# PI_Shield.net
KiCad netlist of a schematic drawn in EAGLE
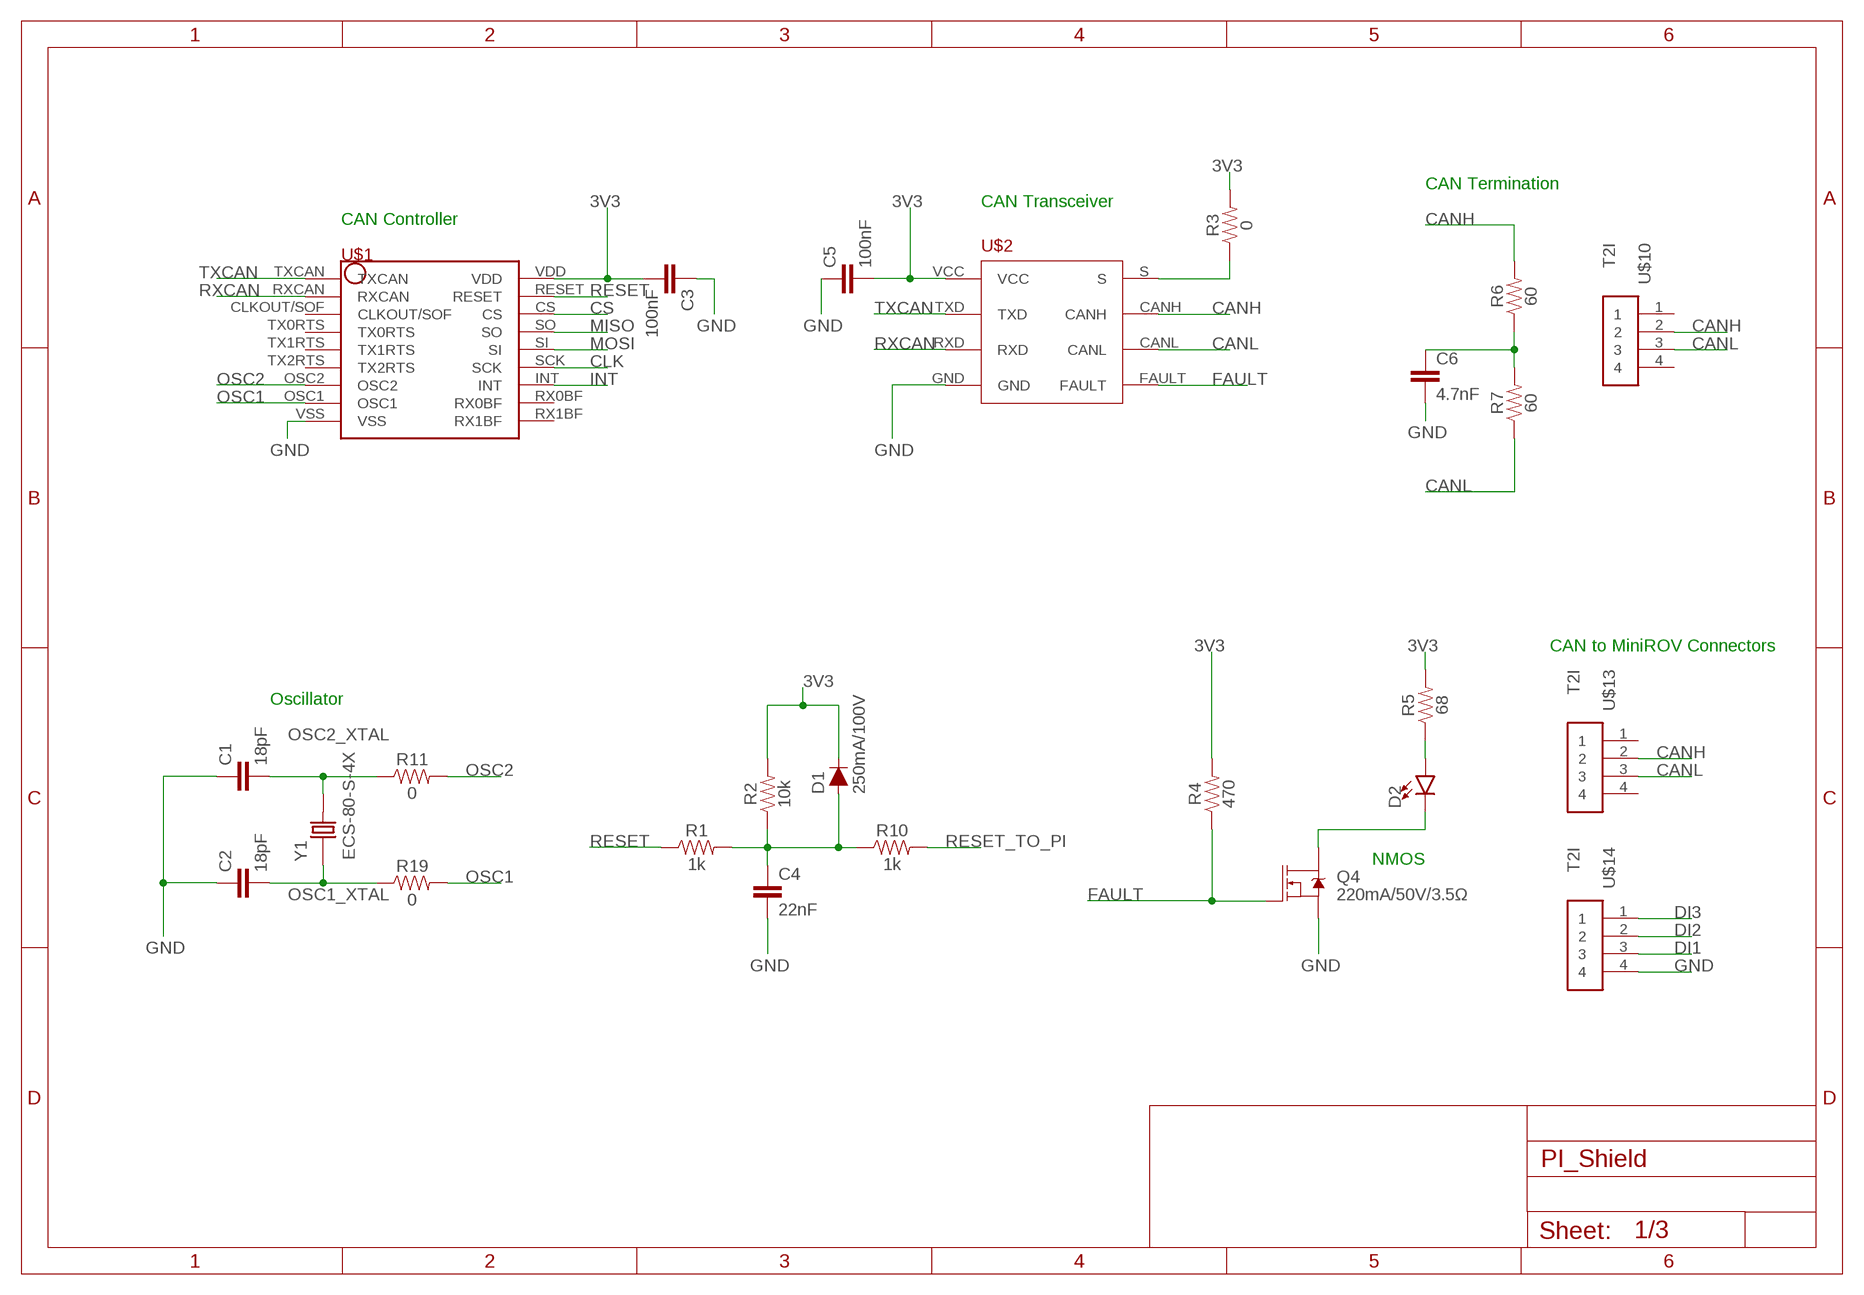
[diagram p0: schematic, sheet 1]
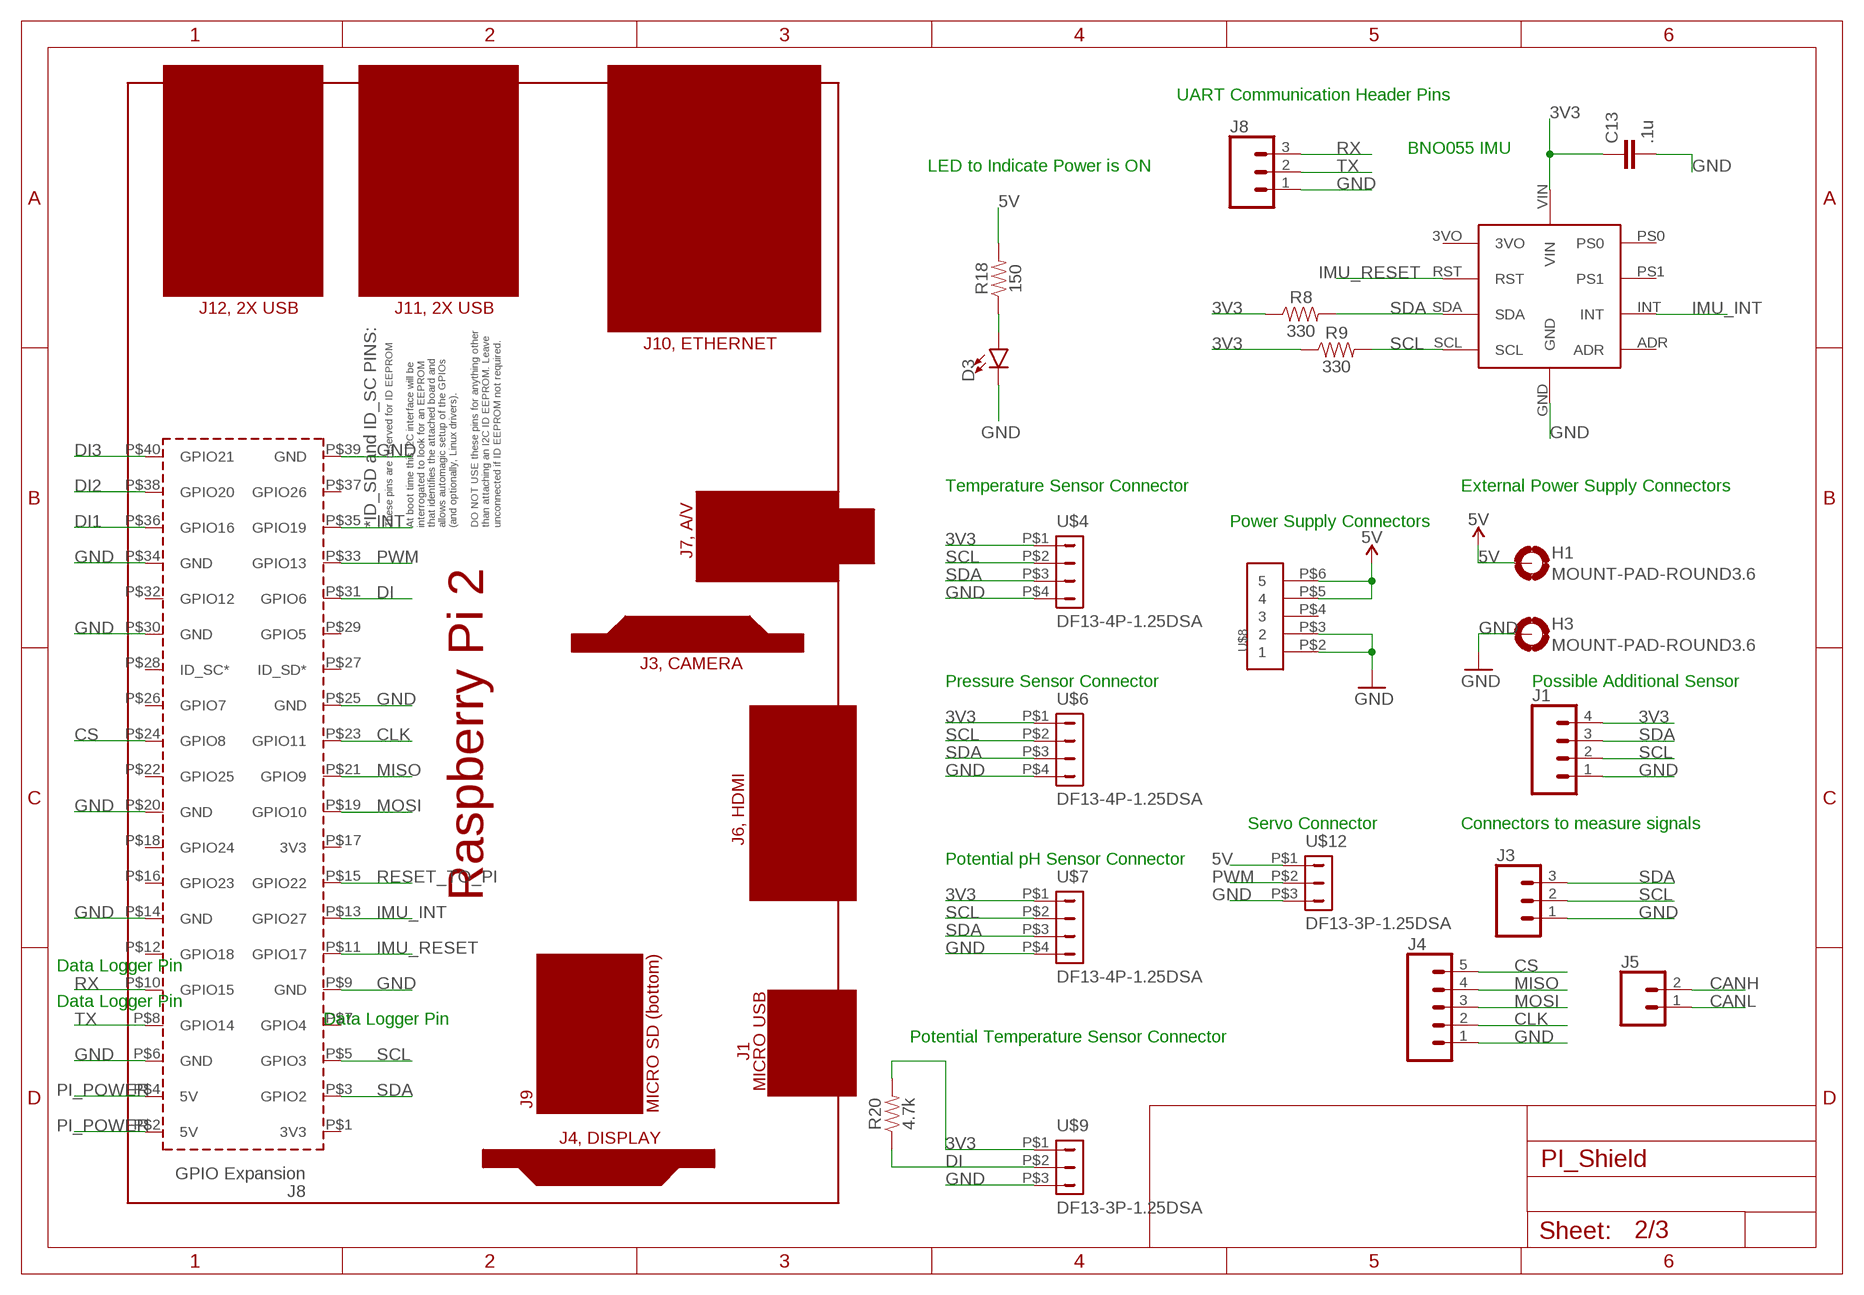
[diagram p1: schematic, sheet 2]
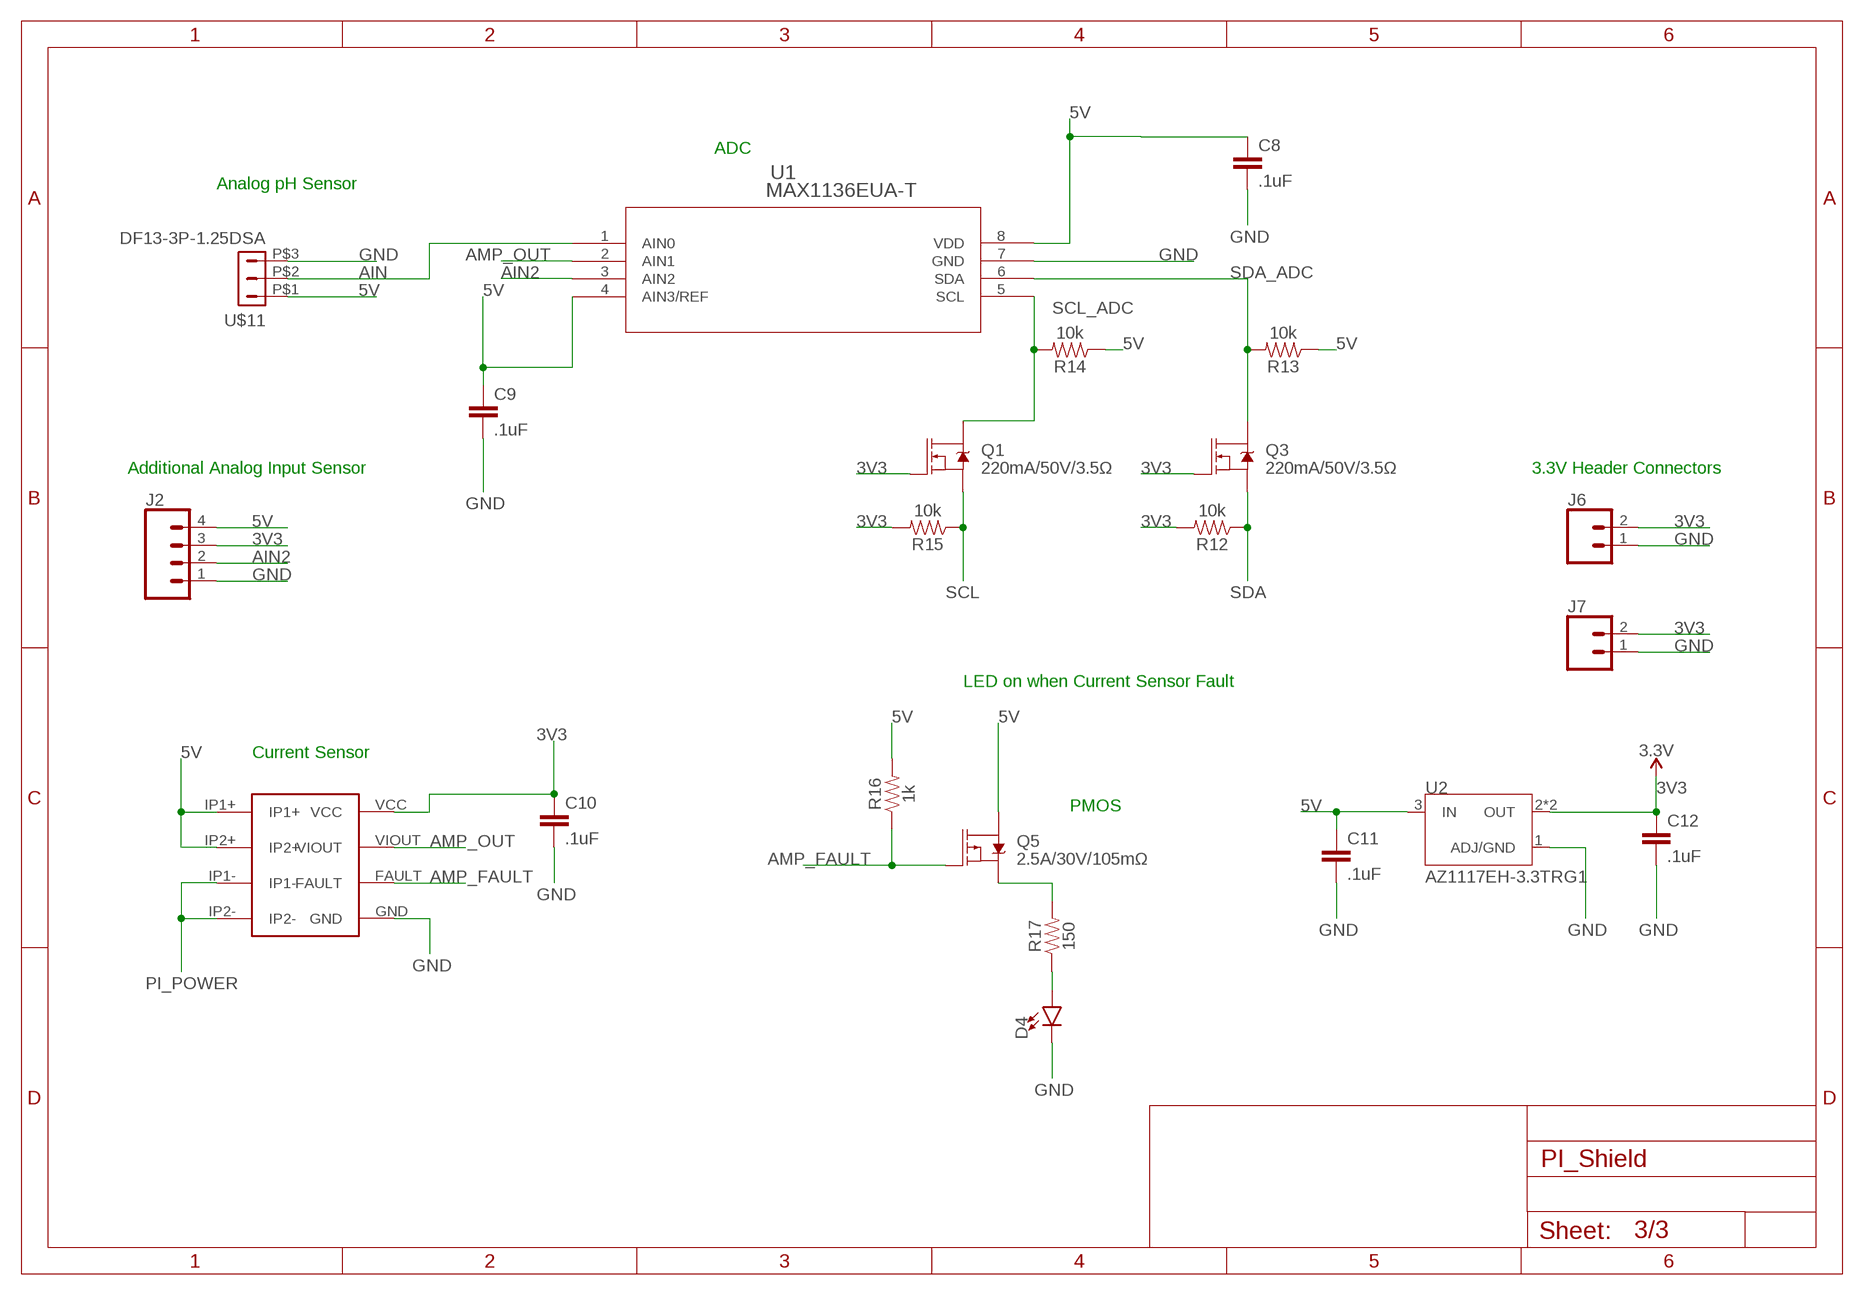
[diagram p2: schematic, sheet 3]

(export (version "E")
  (design (tool "Eeschema 10.0.6"))
  (components
    (comp (ref "C8")
      (value ".1uF")
      (footprint "eagle-import:0603")
      (libsource (lib "eagle-import") (part "22NF/22,000PF-0603-50V-10%"))
    )
    (comp (ref "C9")
      (value ".1uF")
      (footprint "eagle-import:0603")
      (libsource (lib "eagle-import") (part "22NF/22,000PF-0603-50V-10%"))
    )
    (comp (ref "C10")
      (value ".1uF")
      (footprint "eagle-import:0603")
      (libsource (lib "eagle-import") (part "22NF/22,000PF-0603-50V-10%"))
    )
    (comp (ref "C11")
      (value ".1uF")
      (footprint "eagle-import:0603")
      (libsource (lib "eagle-import") (part "22NF/22,000PF-0603-50V-10%"))
    )
    (comp (ref "C12")
      (value ".1uF")
      (footprint "eagle-import:0603")
      (libsource (lib "eagle-import") (part "22NF/22,000PF-0603-50V-10%"))
    )
    (comp (ref "D4")
      (value "LED0603")
      (footprint "eagle-import:LED-0603")
      (libsource (lib "eagle-import") (part "LED0603"))
    )
    (comp (ref "J2")
      (value "CONN_04")
      (footprint "eagle-import:1X04")
      (libsource (lib "eagle-import") (part "CONN_04"))
    )
    (comp (ref "J6")
      (value "CONN_02")
      (footprint "eagle-import:1X02")
      (libsource (lib "eagle-import") (part "CONN_02"))
    )
    (comp (ref "J7")
      (value "CONN_02")
      (footprint "eagle-import:1X02")
      (libsource (lib "eagle-import") (part "CONN_02"))
    )
    (comp (ref "Q1")
      (value "220mA/50V/3.5Ω")
      (footprint "eagle-import:SOT23-3")
      (libsource (lib "eagle-import") (part "MOSFET-NCH-BSS138"))
    )
    (comp (ref "Q3")
      (value "220mA/50V/3.5Ω")
      (footprint "eagle-import:SOT23-3")
      (libsource (lib "eagle-import") (part "MOSFET-NCH-BSS138"))
    )
    (comp (ref "Q5")
      (value "2.5A/30V/105mΩ")
      (footprint "eagle-import:SOT23-3")
      (libsource (lib "eagle-import") (part "MOSFET_PCH-DMG2307L"))
    )
    (comp (ref "R12")
      (value "10k")
      (footprint "eagle-import:0603")
      (libsource (lib "eagle-import") (part "RESISTOR0603"))
    )
    (comp (ref "R13")
      (value "10k")
      (footprint "eagle-import:0603")
      (libsource (lib "eagle-import") (part "RESISTOR0603"))
    )
    (comp (ref "R14")
      (value "10k")
      (footprint "eagle-import:0603")
      (libsource (lib "eagle-import") (part "RESISTOR0603"))
    )
    (comp (ref "R15")
      (value "10k")
      (footprint "eagle-import:0603")
      (libsource (lib "eagle-import") (part "RESISTOR0603"))
    )
    (comp (ref "R16")
      (value "1k")
      (footprint "eagle-import:0603")
      (libsource (lib "eagle-import") (part "RESISTOR0603"))
    )
    (comp (ref "R17")
      (value "150")
      (footprint "eagle-import:0603")
      (libsource (lib "eagle-import") (part "RESISTOR0603"))
    )
    (comp (ref "U$5")
      (value "ACS711")
      (footprint "eagle-import:ACS711")
      (libsource (lib "eagle-import") (part "ACS711"))
    )
    (comp (ref "U$11")
      (value "DF13-3P-1.25DSA")
      (footprint "eagle-import:DF13-3P-1.25DSA")
      (libsource (lib "eagle-import") (part "DF13-3P-1.25DSA"))
    )
    (comp (ref "U1")
      (value "MAX1136EUA-T")
      (footprint "eagle-import:21-0036K")
      (fields
        (field (name "DIGI-KEY_PART_NUMBER") "MAX1136EUA+-ND")
        (field (name "MF") "Maxim Integrated")
        (field (name "MP") "MAX1136EUA+")
      )
      (libsource (lib "eagle-import") (part "MAX1136EUA-T"))
    )
    (comp (ref "U2")
      (value "AZ1117EH-3.3TRG1")
      (footprint "eagle-import:SOT230P700X180-4N")
      (fields (field (name "MF") "Diodes Inc."))
      (libsource (lib "eagle-import") (part "AZ1117EH-3.3TRG1"))
    )
    (comp (ref "C1")
      (value "18pF")
      (footprint "eagle-import:0603")
      (libsource (lib "eagle-import") (part "22PF-0603-50V-5%"))
    )
    (comp (ref "C2")
      (value "18pF")
      (footprint "eagle-import:0603")
      (libsource (lib "eagle-import") (part "22PF-0603-50V-5%"))
    )
    (comp (ref "C3")
      (value "100nF")
      (footprint "eagle-import:0603")
      (libsource (lib "eagle-import") (part "22NF/22,000PF-0603-50V-10%"))
    )
    (comp (ref "C4")
      (value "22nF")
      (footprint "eagle-import:0603")
      (libsource (lib "eagle-import") (part "22NF/22,000PF-0603-50V-10%"))
    )
    (comp (ref "C5")
      (value "100nF")
      (footprint "eagle-import:0603")
      (libsource (lib "eagle-import") (part "22NF/22,000PF-0603-50V-10%"))
    )
    (comp (ref "C6")
      (value "4.7nF")
      (footprint "eagle-import:0603")
      (libsource (lib "eagle-import") (part "22NF/22,000PF-0603-50V-10%"))
    )
    (comp (ref "D1")
      (value "250mA/100V")
      (footprint "eagle-import:SOD-323")
      (libsource (lib "eagle-import") (part "DIODE-BAS16J"))
    )
    (comp (ref "D2")
      (value "LED0603")
      (footprint "eagle-import:LED-0603")
      (libsource (lib "eagle-import") (part "LED0603"))
    )
    (comp (ref "Q4")
      (value "220mA/50V/3.5Ω")
      (footprint "eagle-import:SOT23-3")
      (libsource (lib "eagle-import") (part "MOSFET-NCH-BSS138"))
    )
    (comp (ref "R1")
      (value "1k")
      (footprint "eagle-import:0603")
      (libsource (lib "eagle-import") (part "RESISTOR0603"))
    )
    (comp (ref "R2")
      (value "10k")
      (footprint "eagle-import:0603")
      (libsource (lib "eagle-import") (part "RESISTOR0603"))
    )
    (comp (ref "R3")
      (value "0")
      (footprint "eagle-import:0603")
      (libsource (lib "eagle-import") (part "RESISTOR0603"))
    )
    (comp (ref "R4")
      (value "470")
      (footprint "eagle-import:0603")
      (libsource (lib "eagle-import") (part "RESISTOR0603"))
    )
    (comp (ref "R5")
      (value "68")
      (footprint "eagle-import:0603")
      (libsource (lib "eagle-import") (part "RESISTOR0603"))
    )
    (comp (ref "R6")
      (value "60")
      (footprint "eagle-import:0603")
      (libsource (lib "eagle-import") (part "RESISTOR0603"))
    )
    (comp (ref "R7")
      (value "60")
      (footprint "eagle-import:0603")
      (libsource (lib "eagle-import") (part "RESISTOR0603"))
    )
    (comp (ref "R10")
      (value "1k")
      (footprint "eagle-import:0603")
      (libsource (lib "eagle-import") (part "RESISTOR0603"))
    )
    (comp (ref "R11")
      (value "0")
      (footprint "eagle-import:0603")
      (libsource (lib "eagle-import") (part "RESISTOR0603"))
    )
    (comp (ref "R19")
      (value "0")
      (footprint "eagle-import:0603")
      (libsource (lib "eagle-import") (part "RESISTOR0603"))
    )
    (comp (ref "U$1")
      (value "MCP2515")
      (footprint "eagle-import:MCP2515")
      (libsource (lib "eagle-import") (part "MCP2515"))
    )
    (comp (ref "U$2")
      (value "TCAN337D")
      (footprint "eagle-import:TCAN337D")
      (libsource (lib "eagle-import") (part "TCAN337D"))
    )
    (comp (ref "U$10")
      (value "T2I")
      (footprint "eagle-import:T2I")
      (libsource (lib "eagle-import") (part "T2I"))
    )
    (comp (ref "U$13")
      (value "T2I")
      (footprint "eagle-import:T2I")
      (libsource (lib "eagle-import") (part "T2I"))
    )
    (comp (ref "U$14")
      (value "T2I")
      (footprint "eagle-import:T2I")
      (libsource (lib "eagle-import") (part "T2I"))
    )
    (comp (ref "Y1")
      (value "ECS-80-S-4X")
      (footprint "eagle-import:XTAL_ECS-80-S-4X")
      (fields (field (name "DIGI-KEY_PART_NUMBER") "X1057-ND") (field (name "MF") "ECS International"))
      (libsource (lib "eagle-import") (part "ECS-80-S-4X"))
    )
    (comp (ref "C13")
      (value ".1u")
      (footprint "eagle-import:0603")
      (libsource (lib "eagle-import") (part "22NF/22,000PF-0603-50V-10%"))
    )
    (comp (ref "D3")
      (value "LED0603")
      (footprint "eagle-import:LED-0603")
      (libsource (lib "eagle-import") (part "LED0603"))
    )
    (comp (ref "H1")
      (value "MOUNT-PAD-ROUND3.6")
      (footprint "eagle-import:3,6-PAD")
      (libsource (lib "eagle-import") (part "MOUNT-PAD-ROUND3.6"))
    )
    (comp (ref "H3")
      (value "MOUNT-PAD-ROUND3.6")
      (footprint "eagle-import:3,6-PAD")
      (libsource (lib "eagle-import") (part "MOUNT-PAD-ROUND3.6"))
    )
    (comp (ref "J1")
      (value "CONN_04")
      (footprint "eagle-import:1X04")
      (libsource (lib "eagle-import") (part "CONN_04"))
    )
    (comp (ref "J3")
      (value "CONN_03")
      (footprint "eagle-import:1X03")
      (libsource (lib "eagle-import") (part "CONN_03"))
    )
    (comp (ref "J4")
      (value "CONN_05")
      (footprint "eagle-import:1X05")
      (libsource (lib "eagle-import") (part "CONN_05"))
    )
    (comp (ref "J5")
      (value "CONN_02")
      (footprint "eagle-import:1X02")
      (libsource (lib "eagle-import") (part "SparkFun-Connectors_513_CONN_02"))
    )
    (comp (ref "J8")
      (value "CONN_03")
      (footprint "eagle-import:1X03")
      (libsource (lib "eagle-import") (part "CONN_03"))
    )
    (comp (ref "PCB1")
      (value "RPI2")
      (footprint "eagle-import:RPI2")
      (libsource (lib "eagle-import") (part "RPI2"))
    )
    (comp (ref "R8")
      (value "330")
      (footprint "eagle-import:0603")
      (libsource (lib "eagle-import") (part "RESISTOR0603"))
    )
    (comp (ref "R9")
      (value "330")
      (footprint "eagle-import:0603")
      (libsource (lib "eagle-import") (part "RESISTOR0603"))
    )
    (comp (ref "R18")
      (value "150")
      (footprint "eagle-import:0603")
      (libsource (lib "eagle-import") (part "RESISTOR0603"))
    )
    (comp (ref "R20")
      (value "4.7k")
      (footprint "eagle-import:0603")
      (libsource (lib "eagle-import") (part "RESISTOR0603"))
    )
    (comp (ref "U$3")
      (value "BNO055_9DOF_BREAKOUT")
      (footprint "eagle-import:BNO055")
      (libsource (lib "eagle-import") (part "BNO055_9DOF_BREAKOUT"))
    )
    (comp (ref "U$4")
      (value "DF13-4P-1.25DSA")
      (footprint "eagle-import:DF13-4P-1.25DSA")
      (libsource (lib "eagle-import") (part "DF13-4P-1.25DSA"))
    )
    (comp (ref "U$6")
      (value "DF13-4P-1.25DSA")
      (footprint "eagle-import:DF13-4P-1.25DSA")
      (libsource (lib "eagle-import") (part "DF13-4P-1.25DSA"))
    )
    (comp (ref "U$7")
      (value "DF13-4P-1.25DSA")
      (footprint "eagle-import:DF13-4P-1.25DSA")
      (libsource (lib "eagle-import") (part "DF13-4P-1.25DSA"))
    )
    (comp (ref "U$8")
      (value "T2I5P")
      (footprint "eagle-import:T2I5P")
      (libsource (lib "eagle-import") (part "T2I5P"))
    )
    (comp (ref "U$9")
      (value "DF13-3P-1.25DSA")
      (footprint "eagle-import:DF13-3P-1.25DSA")
      (libsource (lib "eagle-import") (part "DF13-3P-1.25DSA"))
    )
    (comp (ref "U$12")
      (value "DF13-3P-1.25DSA")
      (footprint "eagle-import:DF13-3P-1.25DSA")
      (libsource (lib "eagle-import") (part "DF13-3P-1.25DSA"))
    )
  )
  (nets
    (net (code "1") (name "3V3") (class "Default")
      (node (ref "C10") (pin "1") (pinfunction "1_1") (pintype "passive"))
      (node (ref "C12") (pin "1") (pinfunction "1_1") (pintype "passive"))
      (node (ref "C13") (pin "1") (pinfunction "1_1") (pintype "passive"))
      (node (ref "C3") (pin "2") (pinfunction "2_2") (pintype "passive"))
      (node (ref "C5") (pin "2") (pinfunction "2_2") (pintype "passive"))
      (node (ref "D1") (pin "C") (pinfunction "C_C") (pintype "passive"))
      (node (ref "J1") (pin "4") (pinfunction "4_4") (pintype "passive"))
      (node (ref "J2") (pin "3") (pinfunction "3_3") (pintype "passive"))
      (node (ref "J6") (pin "2") (pinfunction "2_2") (pintype "passive"))
      (node (ref "J7") (pin "2") (pinfunction "2_2") (pintype "passive"))
      (node (ref "Q1") (pin "1") (pinfunction "G_1") (pintype "bidirectional"))
      (node (ref "Q3") (pin "1") (pinfunction "G_1") (pintype "bidirectional"))
      (node (ref "R12") (pin "2") (pinfunction "2_2") (pintype "passive"))
      (node (ref "R15") (pin "2") (pinfunction "2_2") (pintype "passive"))
      (node (ref "R2") (pin "2") (pinfunction "2_2") (pintype "passive"))
      (node (ref "R20") (pin "2") (pinfunction "2_2") (pintype "passive"))
      (node (ref "R3") (pin "2") (pinfunction "2_2") (pintype "passive"))
      (node (ref "R4") (pin "2") (pinfunction "2_2") (pintype "passive"))
      (node (ref "R5") (pin "2") (pinfunction "2_2") (pintype "passive"))
      (node (ref "R8") (pin "1") (pinfunction "1_1") (pintype "passive"))
      (node (ref "R9") (pin "1") (pinfunction "1_1") (pintype "passive"))
      (node (ref "U$1") (pin "VDD") (pinfunction "VDD_VDD") (pintype "bidirectional"))
      (node (ref "U$2") (pin "VCC") (pinfunction "VCC_VCC") (pintype "bidirectional"))
      (node (ref "U$3") (pin "VIN") (pinfunction "VIN_VIN") (pintype "bidirectional"))
      (node (ref "U$4") (pin "P$1") (pinfunction "1_P$1") (pintype "passive"))
      (node (ref "U$5") (pin "VCC") (pinfunction "VCC_VCC") (pintype "bidirectional"))
      (node (ref "U$6") (pin "P$1") (pinfunction "1_P$1") (pintype "passive"))
      (node (ref "U$7") (pin "P$1") (pinfunction "1_P$1") (pintype "passive"))
      (node (ref "U$9") (pin "P$1") (pinfunction "1_P$1") (pintype "passive"))
      (node (ref "U2") (pin "2") (pinfunction "OUT_2") (pintype "output"))
      (node (ref "U2") (pin "4") (pinfunction "OUT_4") (pintype "output"))
    )
    (net (code "2") (name "5V") (class "Default")
      (node (ref "C11") (pin "1") (pinfunction "1_1") (pintype "passive"))
      (node (ref "C8") (pin "1") (pinfunction "1_1") (pintype "passive"))
      (node (ref "C9") (pin "1") (pinfunction "1_1") (pintype "passive"))
      (node (ref "H1") (pin "B3,6") (pinfunction "MOUNT_B3,6") (pintype "passive"))
      (node (ref "J2") (pin "4") (pinfunction "4_4") (pintype "passive"))
      (node (ref "Q5") (pin "3") (pinfunction "D_3") (pintype "bidirectional"))
      (node (ref "R13") (pin "1") (pinfunction "1_1") (pintype "passive"))
      (node (ref "R14") (pin "1") (pinfunction "1_1") (pintype "passive"))
      (node (ref "R16") (pin "2") (pinfunction "2_2") (pintype "passive"))
      (node (ref "R18") (pin "2") (pinfunction "2_2") (pintype "passive"))
      (node (ref "U$11") (pin "P$1") (pinfunction "1_P$1") (pintype "passive"))
      (node (ref "U$12") (pin "P$1") (pinfunction "1_P$1") (pintype "passive"))
      (node (ref "U$5") (pin "IP1+") (pinfunction "IP1+_IP1+") (pintype "bidirectional"))
      (node (ref "U$5") (pin "IP2+") (pinfunction "IP2+_IP2+") (pintype "bidirectional"))
      (node (ref "U$8") (pin "P$5") (pinfunction "4_P$5") (pintype "bidirectional"))
      (node (ref "U$8") (pin "P$6") (pinfunction "5_P$6") (pintype "bidirectional"))
      (node (ref "U1") (pin "4") (pinfunction "AIN3/REF_4") (pintype "bidirectional"))
      (node (ref "U1") (pin "8") (pinfunction "VDD_8") (pintype "power_in"))
      (node (ref "U2") (pin "3") (pinfunction "IN_3") (pintype "input"))
    )
    (net (code "3") (name "AIN") (class "Default")
      (node (ref "U$11") (pin "P$2") (pinfunction "2_P$2") (pintype "passive"))
      (node (ref "U1") (pin "1") (pinfunction "AIN0_1") (pintype "bidirectional"))
    )
    (net (code "4") (name "AIN2") (class "Default")
      (node (ref "J2") (pin "2") (pinfunction "2_2") (pintype "passive"))
      (node (ref "U1") (pin "3") (pinfunction "AIN2_3") (pintype "bidirectional"))
    )
    (net (code "5") (name "AMP_FAULT") (class "Default")
      (node (ref "Q5") (pin "1") (pinfunction "G_1") (pintype "bidirectional"))
      (node (ref "R16") (pin "1") (pinfunction "1_1") (pintype "passive"))
      (node (ref "U$5") (pin "FAULT") (pinfunction "FAULT_FAULT") (pintype "bidirectional"))
    )
    (net (code "6") (name "AMP_OUT") (class "Default")
      (node (ref "U$5") (pin "VIOUT") (pinfunction "VIOUT_VIOUT") (pintype "bidirectional"))
      (node (ref "U1") (pin "2") (pinfunction "AIN1_2") (pintype "bidirectional"))
    )
    (net (code "7") (name "CANH") (class "Default")
      (node (ref "J5") (pin "2") (pinfunction "2_2") (pintype "passive"))
      (node (ref "R6") (pin "2") (pinfunction "2_2") (pintype "passive"))
      (node (ref "U$10") (pin "2") (pinfunction "2_2") (pintype "bidirectional"))
      (node (ref "U$13") (pin "2") (pinfunction "2_2") (pintype "bidirectional"))
      (node (ref "U$2") (pin "CANH") (pinfunction "CANH_CANH") (pintype "bidirectional"))
    )
    (net (code "8") (name "CANL") (class "Default")
      (node (ref "J5") (pin "1") (pinfunction "1_1") (pintype "passive"))
      (node (ref "R7") (pin "1") (pinfunction "1_1") (pintype "passive"))
      (node (ref "U$10") (pin "3") (pinfunction "3_3") (pintype "bidirectional"))
      (node (ref "U$13") (pin "3") (pinfunction "3_3") (pintype "bidirectional"))
      (node (ref "U$2") (pin "CANL") (pinfunction "CANL_CANL") (pintype "bidirectional"))
    )
    (net (code "9") (name "CLK") (class "Default")
      (node (ref "J4") (pin "2") (pinfunction "2_2") (pintype "passive"))
      (node (ref "PCB1") (pin "P$23") (pinfunction "GPIO11_P$23") (pintype "bidirectional"))
      (node (ref "U$1") (pin "SCK") (pinfunction "SCK_SCK") (pintype "bidirectional"))
    )
    (net (code "10") (name "CS") (class "Default")
      (node (ref "J4") (pin "5") (pinfunction "5_5") (pintype "passive"))
      (node (ref "PCB1") (pin "P$24") (pinfunction "GPIO8_P$24") (pintype "bidirectional"))
      (node (ref "U$1") (pin "CS") (pinfunction "CS_CS") (pintype "bidirectional"))
    )
    (net (code "11") (name "DI") (class "Default")
      (node (ref "PCB1") (pin "P$31") (pinfunction "GPIO6_P$31") (pintype "bidirectional"))
      (node (ref "R20") (pin "1") (pinfunction "1_1") (pintype "passive"))
      (node (ref "U$9") (pin "P$2") (pinfunction "2_P$2") (pintype "passive"))
    )
    (net (code "12") (name "DI1") (class "Default")
      (node (ref "PCB1") (pin "P$36") (pinfunction "GPIO16_P$36") (pintype "bidirectional"))
      (node (ref "U$14") (pin "3") (pinfunction "3_3") (pintype "bidirectional"))
    )
    (net (code "13") (name "DI2") (class "Default")
      (node (ref "PCB1") (pin "P$38") (pinfunction "GPIO20_P$38") (pintype "bidirectional"))
      (node (ref "U$14") (pin "2") (pinfunction "2_2") (pintype "bidirectional"))
    )
    (net (code "14") (name "DI3") (class "Default")
      (node (ref "PCB1") (pin "P$40") (pinfunction "GPIO21_P$40") (pintype "bidirectional"))
      (node (ref "U$14") (pin "1") (pinfunction "1_1") (pintype "bidirectional"))
    )
    (net (code "15") (name "FAULT") (class "Default")
      (node (ref "Q4") (pin "1") (pinfunction "G_1") (pintype "bidirectional"))
      (node (ref "R4") (pin "1") (pinfunction "1_1") (pintype "passive"))
      (node (ref "U$2") (pin "FAULT") (pinfunction "FAULT_FAULT") (pintype "bidirectional"))
    )
    (net (code "16") (name "GND") (class "Default")
      (node (ref "C1") (pin "1") (pinfunction "1_1") (pintype "passive"))
      (node (ref "C10") (pin "2") (pinfunction "2_2") (pintype "passive"))
      (node (ref "C11") (pin "2") (pinfunction "2_2") (pintype "passive"))
      (node (ref "C12") (pin "2") (pinfunction "2_2") (pintype "passive"))
      (node (ref "C13") (pin "2") (pinfunction "2_2") (pintype "passive"))
      (node (ref "C2") (pin "1") (pinfunction "1_1") (pintype "passive"))
      (node (ref "C3") (pin "1") (pinfunction "1_1") (pintype "passive"))
      (node (ref "C4") (pin "2") (pinfunction "2_2") (pintype "passive"))
      (node (ref "C5") (pin "1") (pinfunction "1_1") (pintype "passive"))
      (node (ref "C6") (pin "2") (pinfunction "2_2") (pintype "passive"))
      (node (ref "C8") (pin "2") (pinfunction "2_2") (pintype "passive"))
      (node (ref "C9") (pin "2") (pinfunction "2_2") (pintype "passive"))
      (node (ref "D3") (pin "C") (pinfunction "C_C") (pintype "passive"))
      (node (ref "D4") (pin "C") (pinfunction "C_C") (pintype "passive"))
      (node (ref "H3") (pin "B3,6") (pinfunction "MOUNT_B3,6") (pintype "passive"))
      (node (ref "J1") (pin "1") (pinfunction "1_1") (pintype "passive"))
      (node (ref "J2") (pin "1") (pinfunction "1_1") (pintype "passive"))
      (node (ref "J3") (pin "1") (pinfunction "1_1") (pintype "passive"))
      (node (ref "J4") (pin "1") (pinfunction "1_1") (pintype "passive"))
      (node (ref "J6") (pin "1") (pinfunction "1_1") (pintype "passive"))
      (node (ref "J7") (pin "1") (pinfunction "1_1") (pintype "passive"))
      (node (ref "J8") (pin "1") (pinfunction "1_1") (pintype "passive"))
      (node (ref "PCB1") (pin "P$14") (pinfunction "GND_P$14") (pintype "bidirectional"))
      (node (ref "PCB1") (pin "P$20") (pinfunction "GND_P$20") (pintype "bidirectional"))
      (node (ref "PCB1") (pin "P$25") (pinfunction "GND_P$25") (pintype "bidirectional"))
      (node (ref "PCB1") (pin "P$30") (pinfunction "GND_P$30") (pintype "bidirectional"))
      (node (ref "PCB1") (pin "P$34") (pinfunction "GND_P$34") (pintype "bidirectional"))
      (node (ref "PCB1") (pin "P$39") (pinfunction "GND_P$39") (pintype "bidirectional"))
      (node (ref "PCB1") (pin "P$6") (pinfunction "GND_P$6") (pintype "bidirectional"))
      (node (ref "PCB1") (pin "P$9") (pinfunction "GND_P$9") (pintype "bidirectional"))
      (node (ref "Q4") (pin "2") (pinfunction "S_2") (pintype "bidirectional"))
      (node (ref "U$1") (pin "VSS") (pinfunction "VSS_VSS") (pintype "bidirectional"))
      (node (ref "U$11") (pin "P$3") (pinfunction "3_P$3") (pintype "passive"))
      (node (ref "U$12") (pin "P$3") (pinfunction "3_P$3") (pintype "passive"))
      (node (ref "U$14") (pin "4") (pinfunction "4_4") (pintype "bidirectional"))
      (node (ref "U$2") (pin "GND") (pinfunction "GND_GND") (pintype "bidirectional"))
      (node (ref "U$3") (pin "GND") (pinfunction "GND_GND") (pintype "bidirectional"))
      (node (ref "U$4") (pin "P$4") (pinfunction "4_P$4") (pintype "passive"))
      (node (ref "U$5") (pin "GND") (pinfunction "GND_GND") (pintype "bidirectional"))
      (node (ref "U$6") (pin "P$4") (pinfunction "4_P$4") (pintype "passive"))
      (node (ref "U$7") (pin "P$4") (pinfunction "4_P$4") (pintype "passive"))
      (node (ref "U$8") (pin "P$2") (pinfunction "1_P$2") (pintype "bidirectional"))
      (node (ref "U$8") (pin "P$3") (pinfunction "2_P$3") (pintype "bidirectional"))
      (node (ref "U$9") (pin "P$3") (pinfunction "3_P$3") (pintype "passive"))
      (node (ref "U1") (pin "7") (pinfunction "GND_7") (pintype "power_in"))
      (node (ref "U2") (pin "1") (pinfunction "ADJ/GND_1") (pintype "power_in"))
    )
    (net (code "17") (name "IMU_INT") (class "Default")
      (node (ref "PCB1") (pin "P$13") (pinfunction "GPIO27_P$13") (pintype "bidirectional"))
      (node (ref "U$3") (pin "INT") (pinfunction "INT_INT") (pintype "bidirectional"))
    )
    (net (code "18") (name "IMU_RESET") (class "Default")
      (node (ref "PCB1") (pin "P$11") (pinfunction "GPIO17_P$11") (pintype "bidirectional"))
      (node (ref "U$3") (pin "RST") (pinfunction "RST_RST") (pintype "bidirectional"))
    )
    (net (code "19") (name "INT") (class "Default")
      (node (ref "PCB1") (pin "P$35") (pinfunction "GPIO19_P$35") (pintype "bidirectional"))
      (node (ref "U$1") (pin "INT") (pinfunction "INT_INT") (pintype "bidirectional"))
    )
    (net (code "20") (name "MISO") (class "Default")
      (node (ref "J4") (pin "4") (pinfunction "4_4") (pintype "passive"))
      (node (ref "PCB1") (pin "P$21") (pinfunction "GPIO9_P$21") (pintype "bidirectional"))
      (node (ref "U$1") (pin "SO") (pinfunction "SO_SO") (pintype "bidirectional"))
    )
    (net (code "21") (name "MOSI") (class "Default")
      (node (ref "J4") (pin "3") (pinfunction "3_3") (pintype "passive"))
      (node (ref "PCB1") (pin "P$19") (pinfunction "GPIO10_P$19") (pintype "bidirectional"))
      (node (ref "U$1") (pin "SI") (pinfunction "SI_SI") (pintype "bidirectional"))
    )
    (net (code "22") (name "Net-(C4-Pad1)") (class "Default")
      (node (ref "C4") (pin "1") (pinfunction "1_1") (pintype "passive"))
      (node (ref "D1") (pin "A") (pinfunction "A_A") (pintype "passive"))
      (node (ref "R1") (pin "2") (pinfunction "2_2") (pintype "passive"))
      (node (ref "R10") (pin "1") (pinfunction "1_1") (pintype "passive"))
      (node (ref "R2") (pin "1") (pinfunction "1_1") (pintype "passive"))
    )
    (net (code "23") (name "Net-(C6-Pad1)") (class "Default")
      (node (ref "C6") (pin "1") (pinfunction "1_1") (pintype "passive"))
      (node (ref "R6") (pin "1") (pinfunction "1_1") (pintype "passive"))
      (node (ref "R7") (pin "2") (pinfunction "2_2") (pintype "passive"))
    )
    (net (code "24") (name "Net-(D2-PadA)") (class "Default")
      (node (ref "D2") (pin "A") (pinfunction "A_A") (pintype "passive"))
      (node (ref "R5") (pin "1") (pinfunction "1_1") (pintype "passive"))
    )
    (net (code "25") (name "Net-(D3-PadA)") (class "Default")
      (node (ref "D3") (pin "A") (pinfunction "A_A") (pintype "passive"))
      (node (ref "R18") (pin "1") (pinfunction "1_1") (pintype "passive"))
    )
    (net (code "26") (name "Net-(D4-PadA)") (class "Default")
      (node (ref "D4") (pin "A") (pinfunction "A_A") (pintype "passive"))
      (node (ref "R17") (pin "1") (pinfunction "1_1") (pintype "passive"))
    )
    (net (code "27") (name "Net-(Q4-D)") (class "Default")
      (node (ref "D2") (pin "C") (pinfunction "C_C") (pintype "passive"))
      (node (ref "Q4") (pin "3") (pinfunction "D_3") (pintype "bidirectional"))
    )
    (net (code "28") (name "Net-(Q5-S)") (class "Default")
      (node (ref "Q5") (pin "2") (pinfunction "S_2") (pintype "bidirectional"))
      (node (ref "R17") (pin "2") (pinfunction "2_2") (pintype "passive"))
    )
    (net (code "29") (name "Net-(R3-Pad1)") (class "Default")
      (node (ref "R3") (pin "1") (pinfunction "1_1") (pintype "passive"))
      (node (ref "U$2") (pin "S") (pinfunction "S_S") (pintype "bidirectional"))
    )
    (net (code "30") (name "OSC1") (class "Default")
      (node (ref "R19") (pin "2") (pinfunction "2_2") (pintype "passive"))
      (node (ref "U$1") (pin "OSC1") (pinfunction "OSC1_OSC1") (pintype "bidirectional"))
    )
    (net (code "31") (name "OSC1_XTAL") (class "Default")
      (node (ref "C2") (pin "2") (pinfunction "2_2") (pintype "passive"))
      (node (ref "R19") (pin "1") (pinfunction "1_1") (pintype "passive"))
      (node (ref "Y1") (pin "1") (pinfunction "1_1") (pintype "passive"))
    )
    (net (code "32") (name "OSC2") (class "Default")
      (node (ref "R11") (pin "2") (pinfunction "2_2") (pintype "passive"))
      (node (ref "U$1") (pin "OSC2") (pinfunction "OSC2_OSC2") (pintype "bidirectional"))
    )
    (net (code "33") (name "OSC2_XTAL") (class "Default")
      (node (ref "C1") (pin "2") (pinfunction "2_2") (pintype "passive"))
      (node (ref "R11") (pin "1") (pinfunction "1_1") (pintype "passive"))
      (node (ref "Y1") (pin "2") (pinfunction "2_2") (pintype "passive"))
    )
    (net (code "34") (name "PI_POWER") (class "Default")
      (node (ref "PCB1") (pin "P$2") (pinfunction "5V_P$2") (pintype "bidirectional"))
      (node (ref "PCB1") (pin "P$4") (pinfunction "5V_P$4") (pintype "bidirectional"))
      (node (ref "U$5") (pin "IP1-") (pinfunction "IP1-_IP1-") (pintype "bidirectional"))
      (node (ref "U$5") (pin "IP2-") (pinfunction "IP2-_IP2-") (pintype "bidirectional"))
    )
    (net (code "35") (name "PWM") (class "Default")
      (node (ref "PCB1") (pin "P$33") (pinfunction "GPIO13_P$33") (pintype "bidirectional"))
      (node (ref "U$12") (pin "P$2") (pinfunction "2_P$2") (pintype "passive"))
    )
    (net (code "36") (name "RESET") (class "Default")
      (node (ref "R1") (pin "1") (pinfunction "1_1") (pintype "passive"))
      (node (ref "U$1") (pin "RESET") (pinfunction "RESET_RESET") (pintype "bidirectional"))
    )
    (net (code "37") (name "RESET_TO_PI") (class "Default")
      (node (ref "PCB1") (pin "P$15") (pinfunction "GPIO22_P$15") (pintype "bidirectional"))
      (node (ref "R10") (pin "2") (pinfunction "2_2") (pintype "passive"))
    )
    (net (code "38") (name "RX") (class "Default")
      (node (ref "J8") (pin "3") (pinfunction "3_3") (pintype "passive"))
      (node (ref "PCB1") (pin "P$10") (pinfunction "GPIO15_P$10") (pintype "bidirectional"))
    )
    (net (code "39") (name "RXCAN") (class "Default")
      (node (ref "U$1") (pin "RXCAN") (pinfunction "RXCAN_RXCAN") (pintype "bidirectional"))
      (node (ref "U$2") (pin "RXD") (pinfunction "RXD_RXD") (pintype "bidirectional"))
    )
    (net (code "40") (name "SCL") (class "Default")
      (node (ref "J1") (pin "2") (pinfunction "2_2") (pintype "passive"))
      (node (ref "J3") (pin "2") (pinfunction "2_2") (pintype "passive"))
      (node (ref "PCB1") (pin "P$5") (pinfunction "GPIO3_P$5") (pintype "bidirectional"))
      (node (ref "Q1") (pin "2") (pinfunction "S_2") (pintype "bidirectional"))
      (node (ref "R15") (pin "1") (pinfunction "1_1") (pintype "passive"))
      (node (ref "R9") (pin "2") (pinfunction "2_2") (pintype "passive"))
      (node (ref "U$3") (pin "SCL") (pinfunction "SCL_SCL") (pintype "bidirectional"))
      (node (ref "U$4") (pin "P$2") (pinfunction "2_P$2") (pintype "passive"))
      (node (ref "U$6") (pin "P$2") (pinfunction "2_P$2") (pintype "passive"))
      (node (ref "U$7") (pin "P$2") (pinfunction "2_P$2") (pintype "passive"))
    )
    (net (code "41") (name "SCL_ADC") (class "Default")
      (node (ref "Q1") (pin "3") (pinfunction "D_3") (pintype "bidirectional"))
      (node (ref "R14") (pin "2") (pinfunction "2_2") (pintype "passive"))
      (node (ref "U1") (pin "5") (pinfunction "SCL_5") (pintype "bidirectional"))
    )
    (net (code "42") (name "SDA") (class "Default")
      (node (ref "J1") (pin "3") (pinfunction "3_3") (pintype "passive"))
      (node (ref "J3") (pin "3") (pinfunction "3_3") (pintype "passive"))
      (node (ref "PCB1") (pin "P$3") (pinfunction "GPIO2_P$3") (pintype "bidirectional"))
      (node (ref "Q3") (pin "2") (pinfunction "S_2") (pintype "bidirectional"))
      (node (ref "R12") (pin "1") (pinfunction "1_1") (pintype "passive"))
      (node (ref "R8") (pin "2") (pinfunction "2_2") (pintype "passive"))
      (node (ref "U$3") (pin "SDA") (pinfunction "SDA_SDA") (pintype "bidirectional"))
      (node (ref "U$4") (pin "P$3") (pinfunction "3_P$3") (pintype "passive"))
      (node (ref "U$6") (pin "P$3") (pinfunction "3_P$3") (pintype "passive"))
      (node (ref "U$7") (pin "P$3") (pinfunction "3_P$3") (pintype "passive"))
    )
    (net (code "43") (name "SDA_ADC") (class "Default")
      (node (ref "Q3") (pin "3") (pinfunction "D_3") (pintype "bidirectional"))
      (node (ref "R13") (pin "2") (pinfunction "2_2") (pintype "passive"))
      (node (ref "U1") (pin "6") (pinfunction "SDA_6") (pintype "bidirectional"))
    )
    (net (code "44") (name "TX") (class "Default")
      (node (ref "J8") (pin "2") (pinfunction "2_2") (pintype "passive"))
      (node (ref "PCB1") (pin "P$8") (pinfunction "GPIO14_P$8") (pintype "bidirectional"))
    )
    (net (code "45") (name "TXCAN") (class "Default")
      (node (ref "U$1") (pin "TXCAN") (pinfunction "TXCAN_TXCAN") (pintype "bidirectional"))
      (node (ref "U$2") (pin "TXD") (pinfunction "TXD_TXD") (pintype "bidirectional"))
    )
    (net (code "46") (name "unconnected-(PCB1-3V3-PadP$1)") (class "Default")
      (node (ref "PCB1") (pin "P$1") (pinfunction "3V3_P$1") (pintype "bidirectional"))
    )
    (net (code "47") (name "unconnected-(PCB1-3V3-PadP$17)") (class "Default")
      (node (ref "PCB1") (pin "P$17") (pinfunction "3V3_P$17") (pintype "bidirectional"))
    )
    (net (code "48") (name "unconnected-(PCB1-GPIO4-PadP$7)") (class "Default")
      (node (ref "PCB1") (pin "P$7") (pinfunction "GPIO4_P$7") (pintype "bidirectional"))
    )
    (net (code "49") (name "unconnected-(PCB1-GPIO5-PadP$29)") (class "Default")
      (node (ref "PCB1") (pin "P$29") (pinfunction "GPIO5_P$29") (pintype "bidirectional"))
    )
    (net (code "50") (name "unconnected-(PCB1-GPIO7-PadP$26)") (class "Default")
      (node (ref "PCB1") (pin "P$26") (pinfunction "GPIO7_P$26") (pintype "bidirectional"))
    )
    (net (code "51") (name "unconnected-(PCB1-GPIO12-PadP$32)") (class "Default")
      (node (ref "PCB1") (pin "P$32") (pinfunction "GPIO12_P$32") (pintype "bidirectional"))
    )
    (net (code "52") (name "unconnected-(PCB1-GPIO18-PadP$12)") (class "Default")
      (node (ref "PCB1") (pin "P$12") (pinfunction "GPIO18_P$12") (pintype "bidirectional"))
    )
    (net (code "53") (name "unconnected-(PCB1-GPIO23-PadP$16)") (class "Default")
      (node (ref "PCB1") (pin "P$16") (pinfunction "GPIO23_P$16") (pintype "bidirectional"))
    )
    (net (code "54") (name "unconnected-(PCB1-GPIO24-PadP$18)") (class "Default")
      (node (ref "PCB1") (pin "P$18") (pinfunction "GPIO24_P$18") (pintype "bidirectional"))
    )
    (net (code "55") (name "unconnected-(PCB1-GPIO25-PadP$22)") (class "Default")
      (node (ref "PCB1") (pin "P$22") (pinfunction "GPIO25_P$22") (pintype "bidirectional"))
    )
    (net (code "56") (name "unconnected-(PCB1-GPIO26-PadP$37)") (class "Default")
      (node (ref "PCB1") (pin "P$37") (pinfunction "GPIO26_P$37") (pintype "bidirectional"))
    )
    (net (code "57") (name "unconnected-(PCB1-ID_SC*-PadP$28)") (class "Default")
      (node (ref "PCB1") (pin "P$28") (pinfunction "ID_SC*_P$28") (pintype "bidirectional"))
    )
    (net (code "58") (name "unconnected-(PCB1-ID_SD*-PadP$27)") (class "Default")
      (node (ref "PCB1") (pin "P$27") (pinfunction "ID_SD*_P$27") (pintype "bidirectional"))
    )
    (net (code "59") (name "unconnected-(U$1-PadCLKOUT{slash}SOF)") (class "Default")
      (node (ref "U$1") (pin "CLKOUT/SOF") (pinfunction "CLKOUT/SOF_CLKOUT/SOF") (pintype "bidirectional"))
    )
    (net (code "60") (name "unconnected-(U$1-PadRX0BF)") (class "Default")
      (node (ref "U$1") (pin "RX0BF") (pinfunction "RX0BF_RX0BF") (pintype "bidirectional"))
    )
    (net (code "61") (name "unconnected-(U$1-PadRX1BF)") (class "Default")
      (node (ref "U$1") (pin "RX1BF") (pinfunction "RX1BF_RX1BF") (pintype "bidirectional"))
    )
    (net (code "62") (name "unconnected-(U$1-PadTX0RTS)") (class "Default")
      (node (ref "U$1") (pin "TX0RTS") (pinfunction "TX0RTS_TX0RTS") (pintype "bidirectional"))
    )
    (net (code "63") (name "unconnected-(U$1-PadTX1RTS)") (class "Default")
      (node (ref "U$1") (pin "TX1RTS") (pinfunction "TX1RTS_TX1RTS") (pintype "bidirectional"))
    )
    (net (code "64") (name "unconnected-(U$1-PadTX2RTS)") (class "Default")
      (node (ref "U$1") (pin "TX2RTS") (pinfunction "TX2RTS_TX2RTS") (pintype "bidirectional"))
    )
    (net (code "65") (name "unconnected-(U$3-Pad3VO)") (class "Default")
      (node (ref "U$3") (pin "3VO") (pinfunction "3VO_3VO") (pintype "bidirectional"))
    )
    (net (code "66") (name "unconnected-(U$3-PadADR)") (class "Default")
      (node (ref "U$3") (pin "ADR") (pinfunction "ADR_ADR") (pintype "bidirectional"))
    )
    (net (code "67") (name "unconnected-(U$3-PadPS0)") (class "Default")
      (node (ref "U$3") (pin "PS0") (pinfunction "PS0_PS0") (pintype "bidirectional"))
    )
    (net (code "68") (name "unconnected-(U$3-PadPS1)") (class "Default")
      (node (ref "U$3") (pin "PS1") (pinfunction "PS1_PS1") (pintype "bidirectional"))
    )
    (net (code "69") (name "unconnected-(U$8-3-PadP$4)") (class "Default")
      (node (ref "U$8") (pin "P$4") (pinfunction "3_P$4") (pintype "bidirectional"))
    )
    (net (code "70") (name "unconnected-(U$10-Pad1)") (class "Default")
      (node (ref "U$10") (pin "1") (pinfunction "1_1") (pintype "bidirectional"))
    )
    (net (code "71") (name "unconnected-(U$10-Pad4)") (class "Default")
      (node (ref "U$10") (pin "4") (pinfunction "4_4") (pintype "bidirectional"))
    )
    (net (code "72") (name "unconnected-(U$13-Pad1)") (class "Default")
      (node (ref "U$13") (pin "1") (pinfunction "1_1") (pintype "bidirectional"))
    )
    (net (code "73") (name "unconnected-(U$13-Pad4)") (class "Default")
      (node (ref "U$13") (pin "4") (pinfunction "4_4") (pintype "bidirectional"))
    )
  )
)
